# LIS331DLTR_-_MEMS_Motion_Sensor_-_Accele.net
KiCad netlist of a schematic drawn in Altium Designer
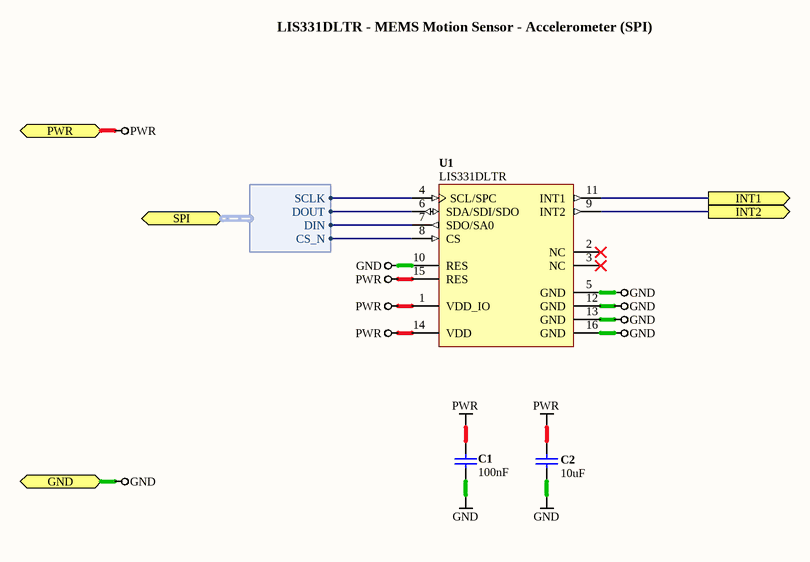
[diagram p0: LIS331DLTR - MEMS Motion Sensor - Accelerometer (SPI).SchDoc]

(export (version "E")
  (design (tool "Eeschema 10.0.6"))
  (components
    (comp (ref "C1")
      (value "100nF")
      (footprint "CAPC0402(1005)60_L")
      (description "CAP 100nF 10V ±10% 0402 (1005 Metric) Thickness 0.6mm SMD")
      (fields (field (name "TOLERANCE") "±10%") (field (name "Comment") "CAP 100nF 10V 0402(1005)"))
      (libsource (lib "Altium Vault") (part "CMP-1034-02065-1"))
    )
    (comp (ref "C2")
      (value "10uF")
      (footprint "CAPC0603(1608)100_L")
      (description "CAP 10uF 10V ±10% 0603 (1608 Metric) Thickness 1mm SMD")
      (fields (field (name "TOLERANCE") "±10%") (field (name "Comment") "CAP 10uF 10V 0603(1608)"))
      (libsource (lib "Altium Vault") (part "CMP-1035-02799-1"))
    )
    (comp (ref "U1")
      (value "LIS331DLTR")
      (footprint "LGA16-3X3X1_L")
      (fields (field (name "MANUFACTURER") "STMicroelectronics"))
      (libsource (lib "Altium Content Vault") (part "CMP-0234-00061-2"))
    )
  )
  (nets
    (net (code "2") (name "/CS_N") (class "Default")
      (node (ref "U1") (pin "8") (pinfunction "CS_8") (pintype "input"))
    )
    (net (code "3") (name "/DIN") (class "Default")
      (node (ref "U1") (pin "7") (pinfunction "SDO/SA0_7") (pintype "output"))
    )
    (net (code "4") (name "/DOUT") (class "Default")
      (node (ref "U1") (pin "6") (pinfunction "SDA/SDI/SDO_6") (pintype "bidirectional"))
    )
    (net (code "5") (name "/INT1") (class "Default")
      (node (ref "U1") (pin "11") (pinfunction "INT1_11") (pintype "output"))
    )
    (net (code "6") (name "/INT2") (class "Default")
      (node (ref "U1") (pin "9") (pinfunction "INT2_9") (pintype "output"))
    )
    (net (code "7") (name "/SCLK") (class "Default")
      (node (ref "U1") (pin "4") (pinfunction "SCL/SPC_4") (pintype "input"))
    )
    (net (code "9") (name "GND") (class "Default")
      (node (ref "C1") (pin "2") (pinfunction "2_2") (pintype "passive"))
      (node (ref "C2") (pin "2") (pinfunction "2_2") (pintype "passive"))
      (node (ref "U1") (pin "10") (pinfunction "RES_10") (pintype "passive"))
      (node (ref "U1") (pin "12") (pinfunction "GND_12") (pintype "power_in"))
      (node (ref "U1") (pin "13") (pinfunction "GND_13") (pintype "power_in"))
      (node (ref "U1") (pin "16") (pinfunction "GND_16") (pintype "power_in"))
      (node (ref "U1") (pin "5") (pinfunction "GND_5") (pintype "power_in"))
    )
    (net (code "10") (name "PWR") (class "Default")
      (node (ref "C1") (pin "1") (pinfunction "1_1") (pintype "passive"))
      (node (ref "C2") (pin "1") (pinfunction "1_1") (pintype "passive"))
      (node (ref "U1") (pin "1") (pinfunction "VDD_IO_1") (pintype "power_in"))
      (node (ref "U1") (pin "14") (pinfunction "VDD_14") (pintype "power_in"))
      (node (ref "U1") (pin "15") (pinfunction "RES_15") (pintype "passive"))
    )
    (net (code "11") (name "unconnected-(U1-NC-Pad2)") (class "Default")
      (node (ref "U1") (pin "2") (pinfunction "NC_2") (pintype "passive+no_connect"))
    )
    (net (code "12") (name "unconnected-(U1-NC-Pad3)") (class "Default")
      (node (ref "U1") (pin "3") (pinfunction "NC_3") (pintype "passive+no_connect"))
    )
  )
)
